# Circuit.net
KiCad netlist of a schematic drawn in EAGLE
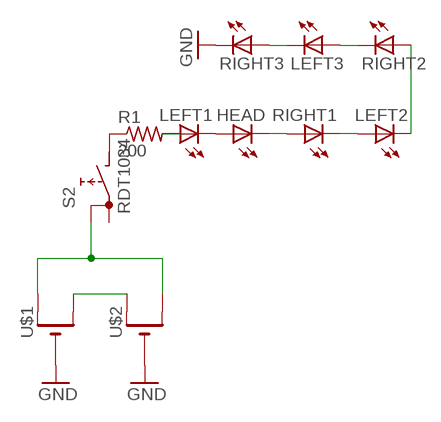
[diagram p0: schematic, sheet 1]

(export (version "E")
  (design (tool "Eeschema 10.0.6"))
  (components
    (comp (ref "HEAD")
      (value "LED3MM")
      (footprint "eagle-import:LED3MM")
      (libsource (lib "eagle-import") (part "LED3MM"))
    )
    (comp (ref "LEFT1")
      (value "LED3MM")
      (footprint "eagle-import:LED3MM")
      (libsource (lib "eagle-import") (part "LED3MM"))
    )
    (comp (ref "LEFT2")
      (value "LED3MM")
      (footprint "eagle-import:LED3MM")
      (libsource (lib "eagle-import") (part "LED3MM"))
    )
    (comp (ref "LEFT3")
      (value "LED3MM")
      (footprint "eagle-import:LED3MM")
      (libsource (lib "eagle-import") (part "LED3MM"))
    )
    (comp (ref "R1")
      (value "200")
      (footprint "eagle-import:0204V")
      (libsource (lib "eagle-import") (part "R-US_0204/2V"))
    )
    (comp (ref "RIGHT1")
      (value "LED3MM")
      (footprint "eagle-import:LED3MM")
      (libsource (lib "eagle-import") (part "LED3MM"))
    )
    (comp (ref "RIGHT2")
      (value "LED3MM")
      (footprint "eagle-import:LED3MM")
      (libsource (lib "eagle-import") (part "LED3MM"))
    )
    (comp (ref "RIGHT3")
      (value "LED3MM")
      (footprint "eagle-import:LED3MM")
      (libsource (lib "eagle-import") (part "LED3MM"))
    )
    (comp (ref "S2")
      (value "RDT1034")
      (footprint "eagle-import:RDT1034")
      (libsource (lib "eagle-import") (part "RDT1034"))
    )
    (comp (ref "U$1")
      (value "CR1220THM")
      (footprint "eagle-import:CR1220-THM")
      (libsource (lib "eagle-import") (part "CR1220THM"))
    )
    (comp (ref "U$2")
      (value "CR1220THM")
      (footprint "eagle-import:CR1220-THM")
      (libsource (lib "eagle-import") (part "CR1220THM"))
    )
  )
  (nets
    (net (code "1") (name "GND") (class "Default")
      (node (ref "RIGHT3") (pin "K") (pinfunction "C_K") (pintype "passive"))
      (node (ref "U$1") (pin "-") (pinfunction "-_-") (pintype "passive"))
      (node (ref "U$2") (pin "-") (pinfunction "-_-") (pintype "passive"))
    )
    (net (code "2") (name "Net-(HEAD-C)") (class "Default")
      (node (ref "HEAD") (pin "K") (pinfunction "C_K") (pintype "passive"))
      (node (ref "RIGHT1") (pin "A") (pinfunction "A_A") (pintype "passive"))
    )
    (net (code "3") (name "Net-(LEFT1-C)") (class "Default")
      (node (ref "HEAD") (pin "A") (pinfunction "A_A") (pintype "passive"))
      (node (ref "LEFT1") (pin "K") (pinfunction "C_K") (pintype "passive"))
    )
    (net (code "4") (name "Net-(LEFT1-PadA)") (class "Default")
      (node (ref "LEFT1") (pin "A") (pinfunction "A_A") (pintype "passive"))
      (node (ref "R1") (pin "2") (pinfunction "2_2") (pintype "passive"))
    )
    (net (code "5") (name "Net-(LEFT2-C)") (class "Default")
      (node (ref "LEFT2") (pin "K") (pinfunction "C_K") (pintype "passive"))
      (node (ref "RIGHT2") (pin "A") (pinfunction "A_A") (pintype "passive"))
    )
    (net (code "6") (name "Net-(LEFT3-C)") (class "Default")
      (node (ref "LEFT3") (pin "K") (pinfunction "C_K") (pintype "passive"))
      (node (ref "RIGHT3") (pin "A") (pinfunction "A_A") (pintype "passive"))
    )
    (net (code "7") (name "Net-(R1-Pad1)") (class "Default")
      (node (ref "R1") (pin "1") (pinfunction "1_1") (pintype "passive"))
      (node (ref "S2") (pin "B") (pinfunction "B_B") (pintype "passive"))
    )
    (net (code "8") (name "Net-(RIGHT1-C)") (class "Default")
      (node (ref "LEFT2") (pin "A") (pinfunction "A_A") (pintype "passive"))
      (node (ref "RIGHT1") (pin "K") (pinfunction "C_K") (pintype "passive"))
    )
    (net (code "9") (name "Net-(RIGHT2-C)") (class "Default")
      (node (ref "LEFT3") (pin "A") (pinfunction "A_A") (pintype "passive"))
      (node (ref "RIGHT2") (pin "K") (pinfunction "C_K") (pintype "passive"))
    )
    (net (code "10") (name "Net-(U$1-+)") (class "Default")
      (node (ref "S2") (pin "A") (pinfunction "A_A") (pintype "passive"))
      (node (ref "U$1") (pin "+1") (pinfunction "+_+1") (pintype "passive"))
      (node (ref "U$2") (pin "+2") (pinfunction "+1_+2") (pintype "passive"))
    )
    (net (code "11") (name "Net-(U$1-+1)") (class "Default")
      (node (ref "U$1") (pin "+2") (pinfunction "+1_+2") (pintype "passive"))
      (node (ref "U$2") (pin "+1") (pinfunction "+_+1") (pintype "passive"))
    )
    (net (code "12") (name "unconnected-(S2-PadA1)") (class "Default")
      (node (ref "S2") (pin "A1") (pinfunction "A1_A1") (pintype "passive"))
    )
  )
)
